# Power.net
KiCad netlist of a schematic drawn in Altium Designer
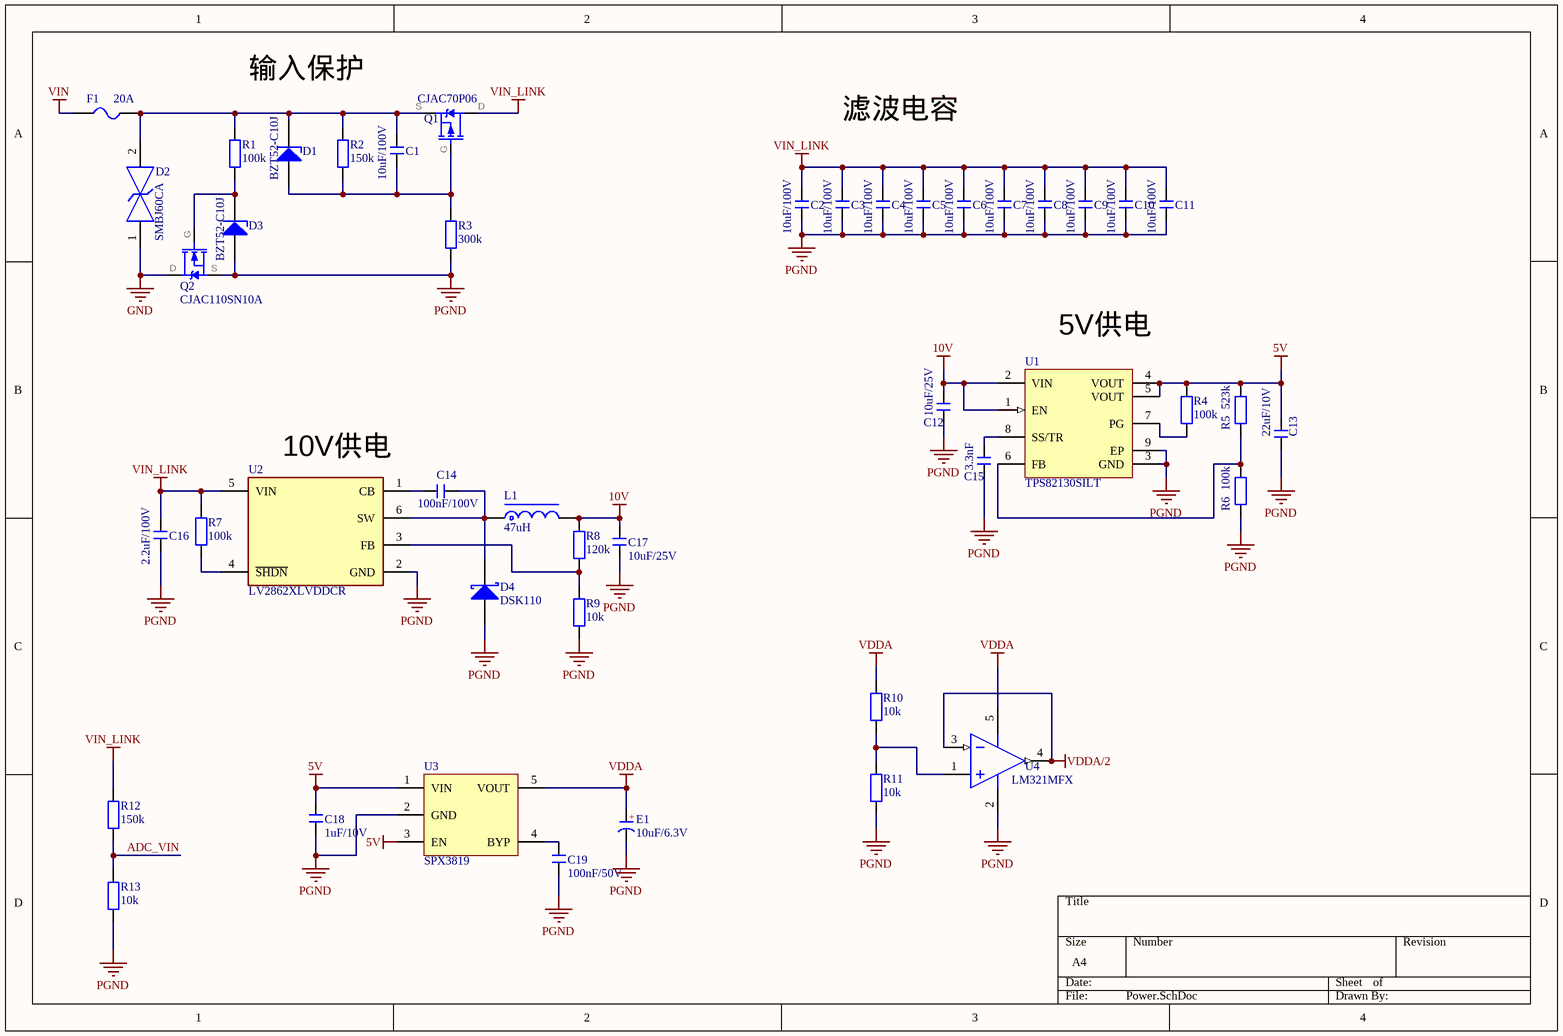
[diagram p0: Power.SchDoc]

(export (version "E")
  (design (tool "Eeschema 10.0.6"))
  (components
    (comp (ref "C1")
      (value "10uF/100V")
      (footprint "Capacitor_1206_SMD")
      (description "无极性贴片电容")
      (fields (field (name "版权归属") "源创客"))
      (libsource (lib "源创客") (part "C"))
    )
    (comp (ref "C2")
      (value "10uF/100V")
      (footprint "Capacitor_1206_SMD")
      (description "无极性贴片电容")
      (fields (field (name "版权归属") "源创客"))
      (libsource (lib "源创客") (part "C"))
    )
    (comp (ref "C3")
      (value "10uF/100V")
      (footprint "Capacitor_1206_SMD")
      (description "无极性贴片电容")
      (fields (field (name "版权归属") "源创客"))
      (libsource (lib "源创客") (part "C"))
    )
    (comp (ref "C4")
      (value "10uF/100V")
      (footprint "Capacitor_1206_SMD")
      (description "无极性贴片电容")
      (fields (field (name "版权归属") "源创客"))
      (libsource (lib "源创客") (part "C"))
    )
    (comp (ref "C5")
      (value "10uF/100V")
      (footprint "Capacitor_1206_SMD")
      (description "无极性贴片电容")
      (fields (field (name "版权归属") "源创客"))
      (libsource (lib "源创客") (part "C"))
    )
    (comp (ref "C6")
      (value "10uF/100V")
      (footprint "Capacitor_1206_SMD")
      (description "无极性贴片电容")
      (fields (field (name "版权归属") "源创客"))
      (libsource (lib "源创客") (part "C"))
    )
    (comp (ref "C7")
      (value "10uF/100V")
      (footprint "Capacitor_1206_SMD")
      (description "无极性贴片电容")
      (fields (field (name "版权归属") "源创客"))
      (libsource (lib "源创客") (part "C"))
    )
    (comp (ref "C8")
      (value "10uF/100V")
      (footprint "Capacitor_1206_SMD")
      (description "无极性贴片电容")
      (fields (field (name "版权归属") "源创客"))
      (libsource (lib "源创客") (part "C"))
    )
    (comp (ref "C9")
      (value "10uF/100V")
      (footprint "Capacitor_1206_SMD")
      (description "无极性贴片电容")
      (fields (field (name "版权归属") "源创客"))
      (libsource (lib "源创客") (part "C"))
    )
    (comp (ref "C10")
      (value "10uF/100V")
      (footprint "Capacitor_1206_SMD")
      (description "无极性贴片电容")
      (fields (field (name "版权归属") "源创客"))
      (libsource (lib "源创客") (part "C"))
    )
    (comp (ref "C11")
      (value "10uF/100V")
      (footprint "Capacitor_1206_SMD")
      (description "无极性贴片电容")
      (fields (field (name "版权归属") "源创客"))
      (libsource (lib "源创客") (part "C"))
    )
    (comp (ref "C12")
      (value "10uF/25V")
      (footprint "Capacitor_0603_SMD")
      (description "无极性贴片电容")
      (fields (field (name "版权归属") "源创客"))
      (libsource (lib "源创客") (part "C"))
    )
    (comp (ref "C13")
      (value "22uF/10V")
      (footprint "Capacitor_0603_SMD")
      (description "无极性贴片电容")
      (fields (field (name "版权归属") "源创客"))
      (libsource (lib "源创客") (part "C"))
    )
    (comp (ref "C14")
      (value "100nF/100V")
      (footprint "Capacitor_0603_SMD")
      (description "无极性贴片电容")
      (fields (field (name "版权归属") "源创客"))
      (libsource (lib "源创客") (part "C"))
    )
    (comp (ref "C15")
      (value "3.3nF")
      (footprint "Capacitor_0402_SMD")
      (description "无极性贴片电容")
      (fields (field (name "版权归属") "源创客"))
      (libsource (lib "源创客") (part "C"))
    )
    (comp (ref "C16")
      (value "2.2uF/100V")
      (footprint "Capacitor_1206_SMD")
      (description "无极性贴片电容")
      (fields (field (name "版权归属") "源创客"))
      (libsource (lib "源创客") (part "C"))
    )
    (comp (ref "C17")
      (value "10uF/25V")
      (footprint "Capacitor_0603_SMD")
      (description "无极性贴片电容")
      (fields (field (name "版权归属") "源创客"))
      (libsource (lib "源创客") (part "C"))
    )
    (comp (ref "C18")
      (value "1uF/10V")
      (footprint "Capacitor_0402_SMD")
      (description "无极性贴片电容")
      (fields (field (name "版权归属") "源创客"))
      (libsource (lib "源创客") (part "C"))
    )
    (comp (ref "C19")
      (value "100nF/50V")
      (footprint "Capacitor_0402_SMD")
      (description "无极性贴片电容")
      (fields (field (name "版权归属") "源创客"))
      (libsource (lib "源创客") (part "C"))
    )
    (comp (ref "D1")
      (value "BZT52-C10J")
      (footprint "SOD-123FL")
      (description "Zener Diode")
      (libsource (lib "0.2 - 二极管-TVS-ESD-整流桥") (part "稳压二极管"))
    )
    (comp (ref "D2")
      (value "SMBJ60CA")
      (footprint "FP-SMBJ-CA-MFG")
      (description "TVS DIODE 60V DO214AA")
      (fields
        (field (name "OCTOPART") "https://octopart.com/smbj48ca-littelfuse-350748")
        (field (name "MANUFACTURER PART NUMBER") "SMBJ48CA")
      )
      (libsource (lib "Altium Content Vault") (part "56ff8cd1c13e7322f1ccec039e06f7f"))
    )
    (comp (ref "D3")
      (value "BZT52-C10J")
      (footprint "SOD-123FL")
      (description "Zener Diode")
      (libsource (lib "0.2 - 二极管-TVS-ESD-整流桥") (part "稳压二极管"))
    )
    (comp (ref "D4")
      (value "DSK110")
      (footprint "SOD-123FL")
      (description "肖特基二极管")
      (libsource (lib "0.2 - 二极管-TVS-ESD-整流桥") (part "SS14"))
    )
    (comp (ref "E1")
      (value "10uF/6.3V")
      (footprint "Tantalum_Capacitor_0805_SMD")
      (description "贴片钽电容")
      (fields (field (name "版权归属") "源创客"))
      (libsource (lib "源创客") (part "C-CD"))
    )
    (comp (ref "F1")
      (value "20A")
      (footprint "FU 1808")
      (description "贴片保险丝")
      (fields (field (name "版权归属") "源创客"))
      (libsource (lib "源创客") (part "FU"))
    )
    (comp (ref "L1")
      (value "47uH")
      (footprint "Molded_Inductor_0530")
      (description "贴片功率电感")
      (fields (field (name "版权归属") "源创客"))
      (libsource (lib "源创客") (part "L-CD"))
    )
    (comp (ref "Q1")
      (value "CJAC70P06")
      (footprint "PDFNWB5×6-8L")
      (description "-70A 7.6mΩ@-10V P-Channel Power MOSFET")
      (libsource (lib "Driver") (part "CJAC70P06"))
    )
    (comp (ref "Q2")
      (value "CJAC110SN10A")
      (footprint "PDFNWB5×6-8L")
      (description "110A 3.4mΩ@10V N-Channel Power MOSFET")
      (libsource (lib "Driver") (part "CJAC110SN10A"))
    )
    (comp (ref "R1")
      (value "100k")
      (footprint "Resistor_0402_SMD")
      (description "贴片电阻")
      (fields (field (name "版权归属") "源创客"))
      (libsource (lib "源创客") (part "R"))
    )
    (comp (ref "R2")
      (value "150k")
      (footprint "Resistor_0402_SMD")
      (description "贴片电阻")
      (fields (field (name "版权归属") "源创客"))
      (libsource (lib "源创客") (part "R"))
    )
    (comp (ref "R3")
      (value "300k")
      (footprint "Resistor_0402_SMD")
      (description "贴片电阻")
      (fields (field (name "版权归属") "源创客"))
      (libsource (lib "源创客") (part "R"))
    )
    (comp (ref "R4")
      (value "100k")
      (footprint "Resistor_0402_SMD")
      (description "贴片电阻")
      (fields (field (name "版权归属") "源创客"))
      (libsource (lib "源创客") (part "R"))
    )
    (comp (ref "R5")
      (value "523k")
      (footprint "Resistor_0402_SMD")
      (description "贴片电阻")
      (libsource (lib "源创客") (part "R"))
    )
    (comp (ref "R6")
      (value "100k")
      (footprint "Resistor_0402_SMD")
      (description "贴片电阻")
      (fields (field (name "版权归属") "源创客"))
      (libsource (lib "源创客") (part "R"))
    )
    (comp (ref "R7")
      (value "100k")
      (footprint "Resistor_0402_SMD")
      (description "贴片电阻")
      (fields (field (name "版权归属") "源创客"))
      (libsource (lib "源创客") (part "R"))
    )
    (comp (ref "R8")
      (value "120k")
      (footprint "Resistor_0402_SMD")
      (description "贴片电阻")
      (fields (field (name "版权归属") "源创客"))
      (libsource (lib "源创客") (part "R"))
    )
    (comp (ref "R9")
      (value "10k")
      (footprint "Resistor_0402_SMD")
      (description "贴片电阻")
      (fields (field (name "版权归属") "源创客"))
      (libsource (lib "源创客") (part "R"))
    )
    (comp (ref "R10")
      (value "10k")
      (footprint "Resistor_0402_SMD")
      (description "贴片电阻")
      (fields (field (name "版权归属") "源创客"))
      (libsource (lib "源创客") (part "R"))
    )
    (comp (ref "R11")
      (value "10k")
      (footprint "Resistor_0402_SMD")
      (description "贴片电阻")
      (fields (field (name "版权归属") "源创客"))
      (libsource (lib "源创客") (part "R"))
    )
    (comp (ref "R12")
      (value "150k")
      (footprint "Resistor_0402_SMD")
      (description "贴片电阻")
      (fields (field (name "版权归属") "源创客"))
      (libsource (lib "源创客") (part "R"))
    )
    (comp (ref "R13")
      (value "10k")
      (footprint "Resistor_0402_SMD")
      (description "贴片电阻")
      (fields (field (name "版权归属") "源创客"))
      (libsource (lib "源创客") (part "R"))
    )
    (comp (ref "U1")
      (value "TPS82130SILT")
      (footprint "SIL0008D_V")
      (fields (field (name "MANUFACTURER") "Texas Instruments"))
      (libsource (lib "Altium Content Vault") (part "TI-TPS82130-SIL-8"))
    )
    (comp (ref "U2")
      (value "LV2862XLVDDCR")
      (footprint "FP-DDC0006A-MFG")
      (libsource (lib "Altium Content Vault") (part "121dc64c8900d5d4b1f77199f935d68"))
    )
    (comp (ref "U3")
      (value "SPX3819")
      (footprint "SOT23-5L")
      (description "500mA Low-Noise LDO Voltage Regulator")
      (libsource (lib "Driver") (part "SPX3819"))
    )
    (comp (ref "U4")
      (value "LM321MFX")
      (footprint "DBV0005A_L")
      (description "Low Power Single Op Amp, 5-pin SOT-23")
      (fields (field (name "MANUFACTURER") "Texas Instruments"))
      (libsource (lib "Altium Content Vault") (part "AMP-OPA-LMV551-5"))
    )
  )
  (nets
    (net (code "1") (name "/ADC_VIN") (class "Default")
      (node (ref "R12") (pin "1") (pinfunction "1_1") (pintype "passive"))
      (node (ref "R13") (pin "2") (pinfunction "2_2") (pintype "passive"))
    )
    (net (code "2") (name "5V") (class "Default")
      (node (ref "C13") (pin "2") (pinfunction "2_2") (pintype "passive"))
      (node (ref "C18") (pin "2") (pinfunction "2_2") (pintype "passive"))
      (node (ref "R4") (pin "2") (pinfunction "2_2") (pintype "passive"))
      (node (ref "R5") (pin "2") (pinfunction "2_2") (pintype "passive"))
      (node (ref "U1") (pin "4") (pinfunction "VOUT_4") (pintype "power_in"))
      (node (ref "U1") (pin "5") (pinfunction "VOUT_5") (pintype "power_in"))
      (node (ref "U3") (pin "1") (pinfunction "VIN_1") (pintype "passive"))
      (node (ref "U3") (pin "3") (pinfunction "EN_3") (pintype "passive"))
    )
    (net (code "3") (name "10V") (class "Default")
      (node (ref "C12") (pin "1") (pinfunction "1_1") (pintype "passive"))
      (node (ref "C17") (pin "1") (pinfunction "1_1") (pintype "passive"))
      (node (ref "L1") (pin "2") (pinfunction "2_2") (pintype "passive"))
      (node (ref "R8") (pin "2") (pinfunction "2_2") (pintype "passive"))
      (node (ref "U1") (pin "1") (pinfunction "EN_1") (pintype "input"))
      (node (ref "U1") (pin "2") (pinfunction "VIN_2") (pintype "power_in"))
    )
    (net (code "4") (name "GND") (class "Default")
      (node (ref "D2") (pin "1") (pinfunction "1_1") (pintype "passive"))
      (node (ref "Q2") (pin "D") (pinfunction "D_D") (pintype "passive"))
    )
    (net (code "5") (name "Net-(D1-A)") (class "Default")
      (node (ref "C1") (pin "1") (pinfunction "1_1") (pintype "passive"))
      (node (ref "D1") (pin "1") (pinfunction "A_1") (pintype "passive"))
      (node (ref "Q1") (pin "G") (pinfunction "G_G") (pintype "passive"))
      (node (ref "R2") (pin "1") (pinfunction "1_1") (pintype "passive"))
      (node (ref "R3") (pin "2") (pinfunction "2_2") (pintype "passive"))
    )
    (net (code "6") (name "Net-(D1-K)") (class "Default")
      (node (ref "C1") (pin "2") (pinfunction "2_2") (pintype "passive"))
      (node (ref "D1") (pin "2") (pinfunction "K_2") (pintype "passive"))
      (node (ref "D2") (pin "2") (pinfunction "2_2") (pintype "passive"))
      (node (ref "F1") (pin "2") (pinfunction "2_2") (pintype "passive"))
      (node (ref "Q1") (pin "S") (pinfunction "S_S") (pintype "passive"))
      (node (ref "R1") (pin "2") (pinfunction "2_2") (pintype "passive"))
      (node (ref "R2") (pin "2") (pinfunction "2_2") (pintype "passive"))
    )
    (net (code "7") (name "Net-(D3-K)") (class "Default")
      (node (ref "D3") (pin "2") (pinfunction "K_2") (pintype "passive"))
      (node (ref "Q2") (pin "G") (pinfunction "G_G") (pintype "passive"))
      (node (ref "R1") (pin "1") (pinfunction "1_1") (pintype "passive"))
    )
    (net (code "8") (name "Net-(D4-K)") (class "Default")
      (node (ref "C14") (pin "2") (pinfunction "2_2") (pintype "passive"))
      (node (ref "D4") (pin "2") (pinfunction "K_2") (pintype "passive"))
      (node (ref "L1") (pin "1") (pinfunction "1_1") (pintype "passive"))
      (node (ref "U2") (pin "6") (pinfunction "SW_6") (pintype "passive"))
    )
    (net (code "9") (name "Net-(U1-FB)") (class "Default")
      (node (ref "R5") (pin "1") (pinfunction "1_1") (pintype "passive"))
      (node (ref "R6") (pin "2") (pinfunction "2_2") (pintype "passive"))
      (node (ref "U1") (pin "6") (pinfunction "FB_6") (pintype "passive"))
    )
    (net (code "10") (name "Net-(U1-PG)") (class "Default")
      (node (ref "R4") (pin "1") (pinfunction "1_1") (pintype "passive"))
      (node (ref "U1") (pin "7") (pinfunction "PG_7") (pintype "open_collector"))
    )
    (net (code "11") (name "Net-(U1-SS{slash}TR)") (class "Default")
      (node (ref "C15") (pin "2") (pinfunction "2_2") (pintype "passive"))
      (node (ref "U1") (pin "8") (pinfunction "SS/TR_8") (pintype "passive"))
    )
    (net (code "12") (name "Net-(U2-CB)") (class "Default")
      (node (ref "C14") (pin "1") (pinfunction "1_1") (pintype "passive"))
      (node (ref "U2") (pin "1") (pinfunction "CB_1") (pintype "passive"))
    )
    (net (code "13") (name "Net-(U2-FB)") (class "Default")
      (node (ref "R8") (pin "1") (pinfunction "1_1") (pintype "passive"))
      (node (ref "R9") (pin "1") (pinfunction "1_1") (pintype "passive"))
      (node (ref "U2") (pin "3") (pinfunction "FB_3") (pintype "passive"))
    )
    (net (code "14") (name "Net-(U2-~{SHDN})") (class "Default")
      (node (ref "R7") (pin "1") (pinfunction "1_1") (pintype "passive"))
      (node (ref "U2") (pin "4") (pinfunction "~{SHDN}_4") (pintype "passive"))
    )
    (net (code "15") (name "Net-(U3-BYP)") (class "Default")
      (node (ref "C19") (pin "2") (pinfunction "2_2") (pintype "passive"))
      (node (ref "U3") (pin "4") (pinfunction "BYP_4") (pintype "passive"))
    )
    (net (code "16") (name "Net-(U4-IN+)") (class "Default")
      (node (ref "R10") (pin "2") (pinfunction "2_2") (pintype "passive"))
      (node (ref "R11") (pin "1") (pinfunction "1_1") (pintype "passive"))
      (node (ref "U4") (pin "1") (pinfunction "IN+_1") (pintype "passive"))
    )
    (net (code "17") (name "PGND") (class "Default")
      (node (ref "C10") (pin "1") (pinfunction "1_1") (pintype "passive"))
      (node (ref "C11") (pin "1") (pinfunction "1_1") (pintype "passive"))
      (node (ref "C12") (pin "2") (pinfunction "2_2") (pintype "passive"))
      (node (ref "C13") (pin "1") (pinfunction "1_1") (pintype "passive"))
      (node (ref "C15") (pin "1") (pinfunction "1_1") (pintype "passive"))
      (node (ref "C16") (pin "2") (pinfunction "2_2") (pintype "passive"))
      (node (ref "C17") (pin "2") (pinfunction "2_2") (pintype "passive"))
      (node (ref "C18") (pin "1") (pinfunction "1_1") (pintype "passive"))
      (node (ref "C19") (pin "1") (pinfunction "1_1") (pintype "passive"))
      (node (ref "C2") (pin "1") (pinfunction "1_1") (pintype "passive"))
      (node (ref "C3") (pin "1") (pinfunction "1_1") (pintype "passive"))
      (node (ref "C4") (pin "1") (pinfunction "1_1") (pintype "passive"))
      (node (ref "C5") (pin "1") (pinfunction "1_1") (pintype "passive"))
      (node (ref "C6") (pin "1") (pinfunction "1_1") (pintype "passive"))
      (node (ref "C7") (pin "1") (pinfunction "1_1") (pintype "passive"))
      (node (ref "C8") (pin "1") (pinfunction "1_1") (pintype "passive"))
      (node (ref "C9") (pin "1") (pinfunction "1_1") (pintype "passive"))
      (node (ref "D3") (pin "1") (pinfunction "A_1") (pintype "passive"))
      (node (ref "D4") (pin "1") (pinfunction "A_1") (pintype "passive"))
      (node (ref "E1") (pin "2") (pinfunction "K_2") (pintype "passive"))
      (node (ref "Q2") (pin "S") (pinfunction "S_S") (pintype "passive"))
      (node (ref "R11") (pin "2") (pinfunction "2_2") (pintype "passive"))
      (node (ref "R13") (pin "1") (pinfunction "1_1") (pintype "passive"))
      (node (ref "R3") (pin "1") (pinfunction "1_1") (pintype "passive"))
      (node (ref "R6") (pin "1") (pinfunction "1_1") (pintype "passive"))
      (node (ref "R9") (pin "2") (pinfunction "2_2") (pintype "passive"))
      (node (ref "U1") (pin "3") (pinfunction "GND_3") (pintype "power_in"))
      (node (ref "U1") (pin "9") (pinfunction "EP_9") (pintype "power_in"))
      (node (ref "U2") (pin "2") (pinfunction "GND_2") (pintype "power_in"))
      (node (ref "U3") (pin "2") (pinfunction "GND_2") (pintype "passive"))
      (node (ref "U4") (pin "2") (pinfunction "V-_2") (pintype "power_in"))
    )
    (net (code "18") (name "VDDA") (class "Default")
      (node (ref "E1") (pin "1") (pinfunction "A_1") (pintype "passive"))
      (node (ref "R10") (pin "1") (pinfunction "1_1") (pintype "passive"))
      (node (ref "U3") (pin "5") (pinfunction "VOUT_5") (pintype "passive"))
      (node (ref "U4") (pin "5") (pinfunction "V+_5") (pintype "power_in"))
    )
    (net (code "19") (name "VDDA{slash}2") (class "Default")
      (node (ref "U4") (pin "3") (pinfunction "IN-_3") (pintype "input"))
      (node (ref "U4") (pin "4") (pinfunction "OUT_4") (pintype "output"))
    )
    (net (code "20") (name "VIN") (class "Default")
      (node (ref "F1") (pin "1") (pinfunction "1_1") (pintype "passive"))
    )
    (net (code "21") (name "VIN_LINK") (class "Default")
      (node (ref "C10") (pin "2") (pinfunction "2_2") (pintype "passive"))
      (node (ref "C11") (pin "2") (pinfunction "2_2") (pintype "passive"))
      (node (ref "C16") (pin "1") (pinfunction "1_1") (pintype "passive"))
      (node (ref "C2") (pin "2") (pinfunction "2_2") (pintype "passive"))
      (node (ref "C3") (pin "2") (pinfunction "2_2") (pintype "passive"))
      (node (ref "C4") (pin "2") (pinfunction "2_2") (pintype "passive"))
      (node (ref "C5") (pin "2") (pinfunction "2_2") (pintype "passive"))
      (node (ref "C6") (pin "2") (pinfunction "2_2") (pintype "passive"))
      (node (ref "C7") (pin "2") (pinfunction "2_2") (pintype "passive"))
      (node (ref "C8") (pin "2") (pinfunction "2_2") (pintype "passive"))
      (node (ref "C9") (pin "2") (pinfunction "2_2") (pintype "passive"))
      (node (ref "Q1") (pin "D") (pinfunction "D_D") (pintype "passive"))
      (node (ref "R12") (pin "2") (pinfunction "2_2") (pintype "passive"))
      (node (ref "R7") (pin "2") (pinfunction "2_2") (pintype "passive"))
      (node (ref "U2") (pin "5") (pinfunction "VIN_5") (pintype "power_in"))
    )
  )
)
